# TokTok_WiFi.net
KiCad netlist of a schematic drawn in EAGLE
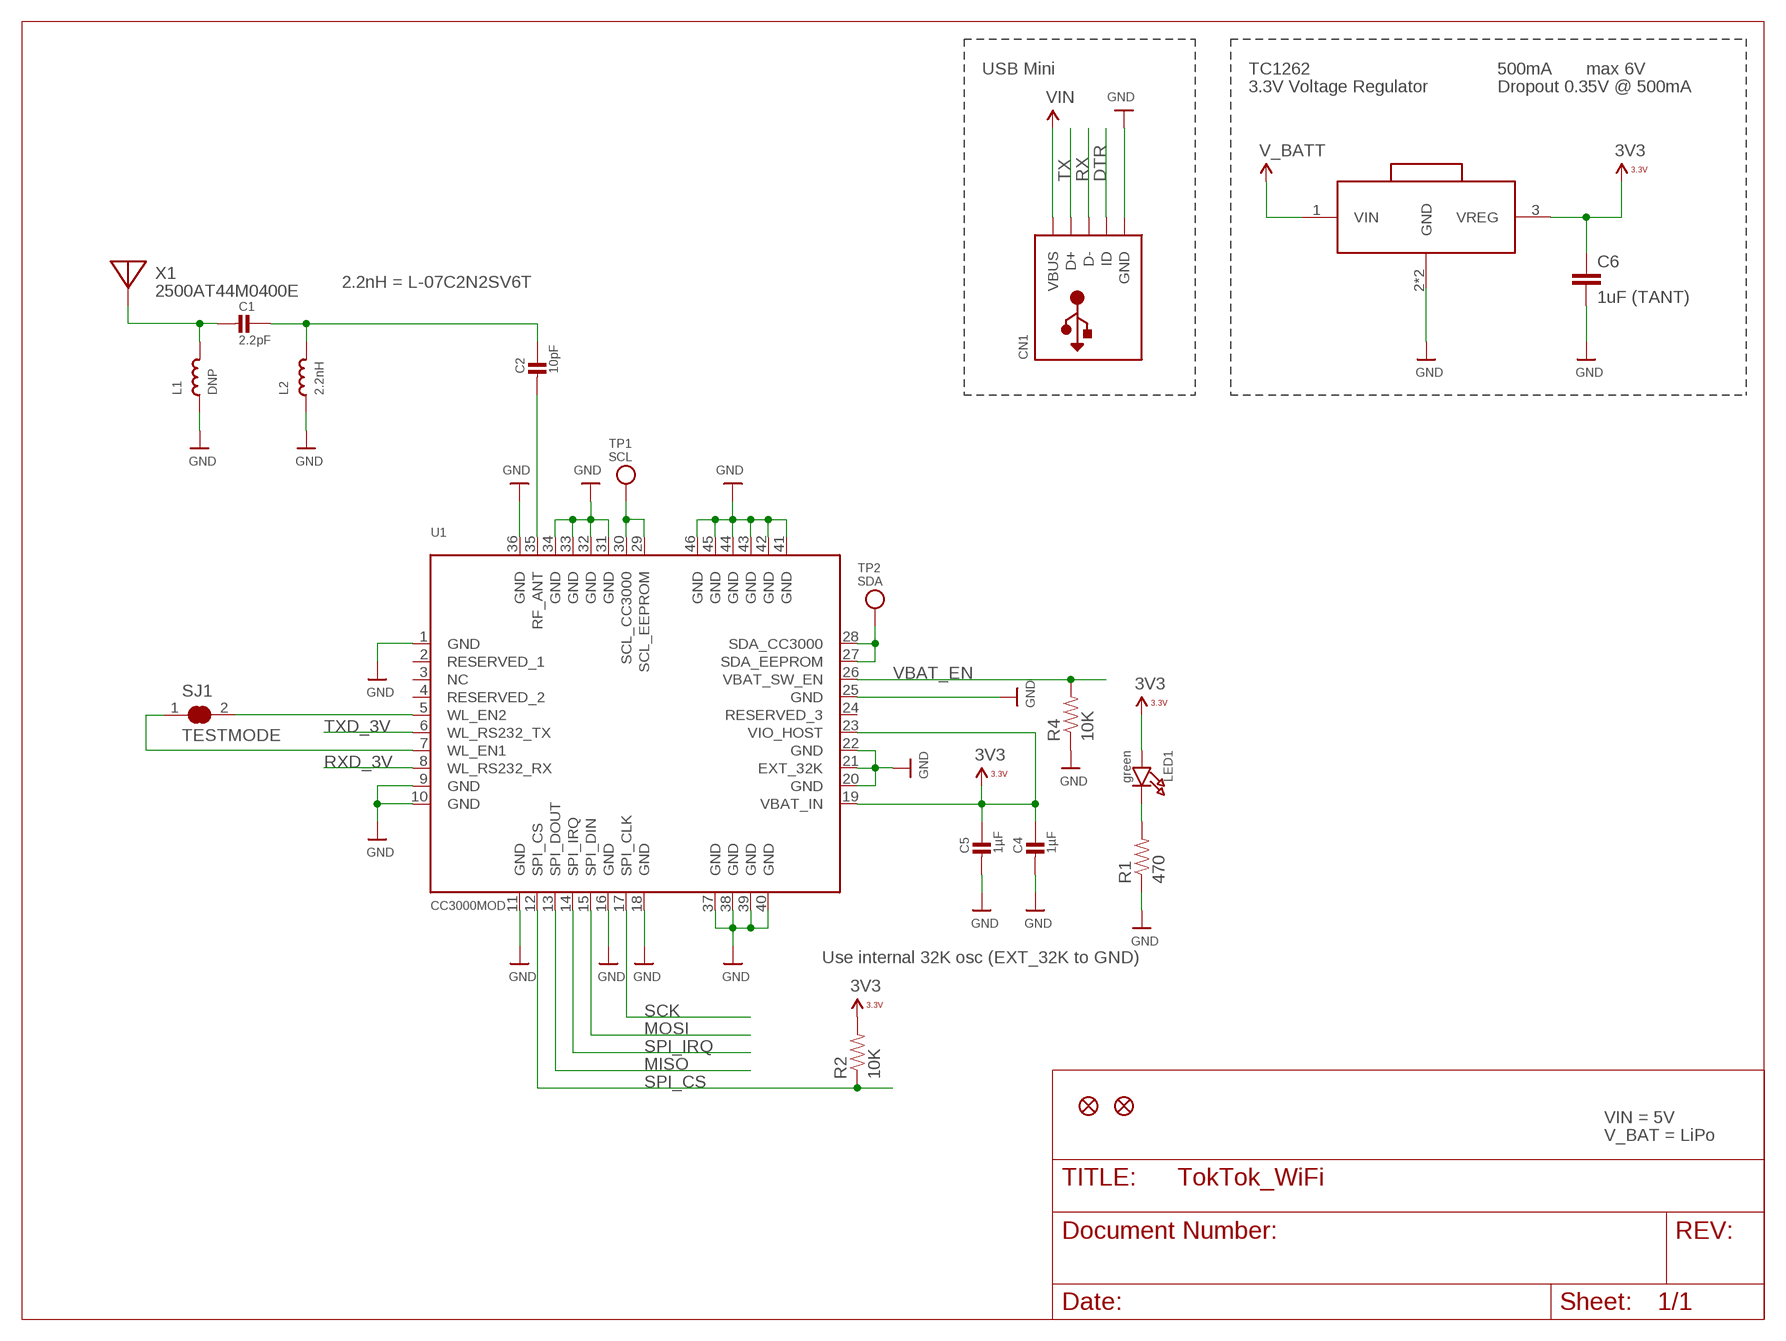
[diagram p0: schematic, sheet 1, part 1 of 2]
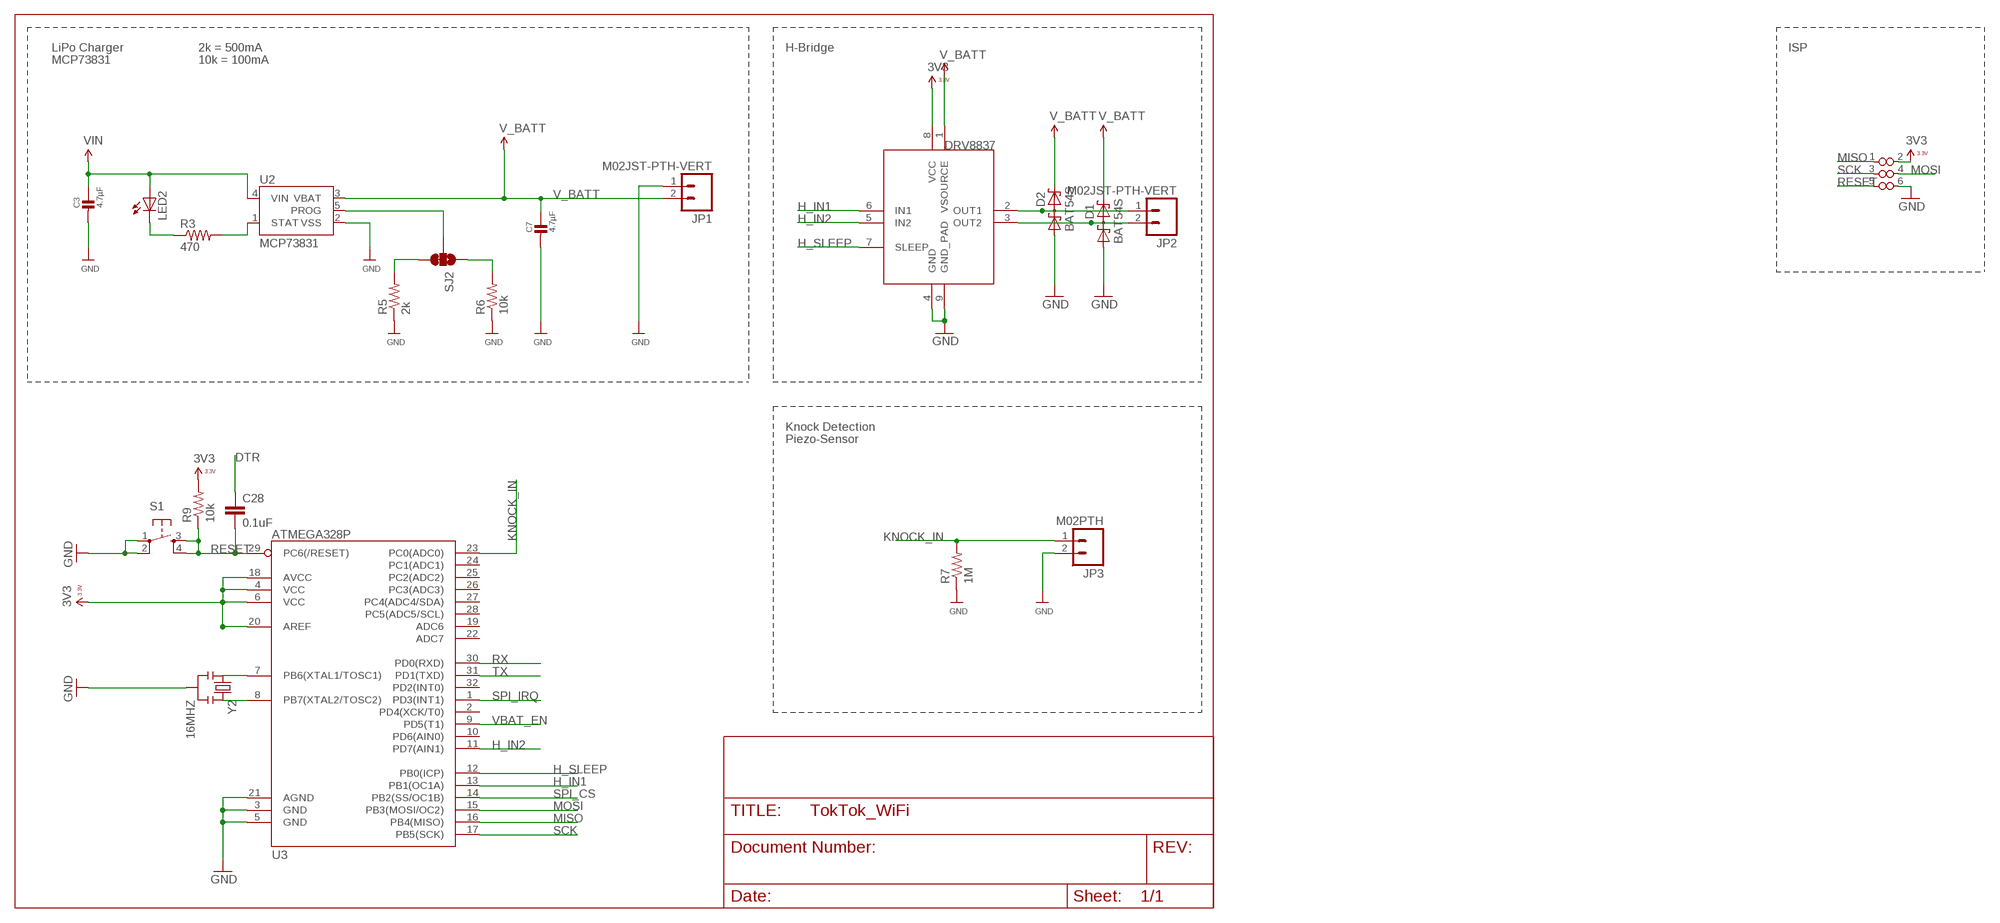
[diagram p1: schematic, sheet 1, part 2 of 2]

(export (version "E")
  (design (tool "Eeschema 10.0.6"))
  (components
    (comp (ref "C1")
      (value "2.2pF")
      (footprint "eagle-import:_0402")
      (libsource (lib "eagle-import") (part "CAP_CERAMIC_0402"))
    )
    (comp (ref "C2")
      (value "10pF")
      (footprint "eagle-import:_0402")
      (libsource (lib "eagle-import") (part "CAP_CERAMIC_0402"))
    )
    (comp (ref "C3")
      (value "4.7µF")
      (footprint "eagle-import:_0805MP")
      (libsource (lib "eagle-import") (part "CAP_CERAMIC_0805MP"))
    )
    (comp (ref "C4")
      (value "1µF")
      (footprint "eagle-import:_0805MP")
      (libsource (lib "eagle-import") (part "CAP_CERAMIC_0805MP"))
    )
    (comp (ref "C5")
      (value "1µF")
      (footprint "eagle-import:_0805MP")
      (libsource (lib "eagle-import") (part "CAP_CERAMIC_0805MP"))
    )
    (comp (ref "C6")
      (value "1uF (TANT)")
      (footprint "eagle-import:1206")
      (libsource (lib "eagle-import") (part "CAP1206"))
    )
    (comp (ref "C7")
      (value "4.7µF")
      (footprint "eagle-import:_0805MP")
      (libsource (lib "eagle-import") (part "CAP_CERAMIC_0805MP"))
    )
    (comp (ref "C28")
      (value "0.1uF")
      (footprint "eagle-import:0805")
      (libsource (lib "eagle-import") (part "CAP0805"))
    )
    (comp (ref "CN1")
      (value "USBMINIB")
      (footprint "eagle-import:USB-MINIB")
      (libsource (lib "eagle-import") (part "USBMINIB"))
    )
    (comp (ref "D1")
      (value "BAT54S")
      (footprint "eagle-import:SOT23")
      (libsource (lib "eagle-import") (part "BAT54S"))
    )
    (comp (ref "D2")
      (value "BAT54S")
      (footprint "eagle-import:SOT23")
      (libsource (lib "eagle-import") (part "BAT54S"))
    )
    (comp (ref "FID1")
      (value "FIDUCIAL\"\"")
      (footprint "eagle-import:FIDUCIAL_1MM")
      (libsource (lib "eagle-import") (part "FIDUCIAL{dblquote}{dblquote}"))
    )
    (comp (ref "FID3")
      (value "FIDUCIAL\"\"")
      (footprint "eagle-import:FIDUCIAL_1MM")
      (fields (field (name "BOM") "EXCLUDE"))
      (libsource (lib "eagle-import") (part "FIDUCIAL{dblquote}{dblquote}"))
    )
    (comp (ref "IC2")
      (value "DRV8837")
      (footprint "eagle-import:WSON-8")
      (libsource (lib "eagle-import") (part "DRV8837"))
    )
    (comp (ref "JP1")
      (value "M02JST-PTH-VERT")
      (footprint "eagle-import:JST-2-PTH-VERT")
      (libsource (lib "eagle-import") (part "M02JST-PTH-VERT"))
    )
    (comp (ref "JP2")
      (value "M02JST-PTH-VERT")
      (footprint "eagle-import:JST-2-PTH-VERT")
      (libsource (lib "eagle-import") (part "M02JST-PTH-VERT"))
    )
    (comp (ref "JP3")
      (value "M02PTH")
      (footprint "eagle-import:1X02")
      (libsource (lib "eagle-import") (part "M02PTH"))
    )
    (comp (ref "L1")
      (value "DNP")
      (footprint "eagle-import:_0402")
      (libsource (lib "eagle-import") (part "INDUCTOR_0402"))
    )
    (comp (ref "L2")
      (value "2.2nH")
      (footprint "eagle-import:_0402")
      (libsource (lib "eagle-import") (part "INDUCTOR_0402"))
    )
    (comp (ref "LED1")
      (value "green")
      (footprint "eagle-import:CHIPLED_0805_NOOUTLINE")
      (libsource (lib "eagle-import") (part "LED0805_NOOUTLINE"))
    )
    (comp (ref "LED2")
      (value "LEDCHIP-LED0805")
      (footprint "eagle-import:CHIP-LED0805")
      (libsource (lib "eagle-import") (part "LEDCHIP-LED0805"))
    )
    (comp (ref "R1")
      (value "470")
      (footprint "eagle-import:0805")
      (libsource (lib "eagle-import") (part "RESISTOR0805-RES"))
    )
    (comp (ref "R2")
      (value "10K")
      (footprint "eagle-import:0805")
      (libsource (lib "eagle-import") (part "RESISTOR0805-RES"))
    )
    (comp (ref "R3")
      (value "470")
      (footprint "eagle-import:0805")
      (libsource (lib "eagle-import") (part "RESISTOR0805-RES"))
    )
    (comp (ref "R4")
      (value "10K")
      (footprint "eagle-import:0805")
      (libsource (lib "eagle-import") (part "RESISTOR0805-RES"))
    )
    (comp (ref "R5")
      (value "2k")
      (footprint "eagle-import:0805")
      (libsource (lib "eagle-import") (part "RESISTOR0805-RES"))
    )
    (comp (ref "R6")
      (value "10k")
      (footprint "eagle-import:0805")
      (libsource (lib "eagle-import") (part "RESISTOR0805-RES"))
    )
    (comp (ref "R7")
      (value "1M")
      (footprint "eagle-import:0805")
      (libsource (lib "eagle-import") (part "RESISTOR0805-RES"))
    )
    (comp (ref "R9")
      (value "10k")
      (footprint "eagle-import:M0805")
      (libsource (lib "eagle-import") (part "R-US_M0805"))
    )
    (comp (ref "S1")
      (value "TAC_SWITCHSMD")
      (footprint "eagle-import:TACTILE-SWITCH-SMD")
      (libsource (lib "eagle-import") (part "TAC_SWITCHSMD"))
    )
    (comp (ref "SJ1")
      (value "TESTMODE")
      (footprint "eagle-import:SOLDERJUMPER_CLOSEDWIRE")
      (libsource (lib "eagle-import") (part "SOLDERJUMPER_CLOSED"))
    )
    (comp (ref "SJ2")
      (value "JUMPER-PAD-3-2OF3_NC_BY_TRACE_SMALL")
      (footprint "eagle-import:PAD-JUMPER-3-2OF3_NC_BY_TRACE_YES_SILK_FULL_BOX")
      (libsource (lib "eagle-import") (part "JUMPER-PAD-3-2OF3_NC_BY_TRACE_SMALL"))
    )
    (comp (ref "TP1")
      (value "SCL")
      (footprint "eagle-import:TESTPOINT_PAD_1MM")
      (libsource (lib "eagle-import") (part "TESTPOINTPAD1MM"))
    )
    (comp (ref "TP2")
      (value "SDA")
      (footprint "eagle-import:TESTPOINT_PAD_1MM")
      (libsource (lib "eagle-import") (part "TESTPOINTPAD1MM"))
    )
    (comp (ref "U$3")
      (value "TC1262")
      (footprint "eagle-import:SOT223")
      (libsource (lib "eagle-import") (part "TC1262"))
    )
    (comp (ref "U$36")
      (value "ISP_POGO")
      (footprint "eagle-import:POGO_ISP")
      (libsource (lib "eagle-import") (part "ISP_POGO"))
    )
    (comp (ref "U1")
      (value "CC3000MOD")
      (footprint "eagle-import:CC3000MOD")
      (libsource (lib "eagle-import") (part "CC3000MOD"))
    )
    (comp (ref "U2")
      (value "MCP73831")
      (footprint "eagle-import:SOT23-5")
      (libsource (lib "eagle-import") (part "MCP73831"))
    )
    (comp (ref "U3")
      (value "ATMEGA328P")
      (footprint "eagle-import:TQFP32-08")
      (libsource (lib "eagle-import") (part "ATMEGA328_SMT"))
    )
    (comp (ref "X1")
      (value "2500AT44M0400E")
      (footprint "eagle-import:ANT_2500AT44M0400")
      (libsource (lib "eagle-import") (part "ANTENNA_JOHANSON_2500AT44M0400"))
    )
    (comp (ref "Y2")
      (value "16MHZ")
      (footprint "eagle-import:RESONATOR-SMD")
      (libsource (lib "eagle-import") (part "RESONATOR8MHZ"))
    )
  )
  (nets
    (net (code "1") (name "/DTR") (class "Default")
      (node (ref "C28") (pin "1") (pinfunction "1_1") (pintype "passive"))
      (node (ref "CN1") (pin "ID") (pinfunction "ID_ID") (pintype "bidirectional"))
    )
    (net (code "2") (name "/H_IN1") (class "Default")
      (node (ref "IC2") (pin "6") (pinfunction "IN1_6") (pintype "bidirectional"))
      (node (ref "U3") (pin "13") (pinfunction "PB1(OC1A)_13") (pintype "bidirectional"))
    )
    (net (code "3") (name "/H_IN2") (class "Default")
      (node (ref "IC2") (pin "5") (pinfunction "IN2_5") (pintype "bidirectional"))
      (node (ref "U3") (pin "11") (pinfunction "PD7(AIN1)_11") (pintype "bidirectional"))
    )
    (net (code "4") (name "/H_SLEEP") (class "Default")
      (node (ref "IC2") (pin "7") (pinfunction "SLEEP_7") (pintype "bidirectional"))
      (node (ref "U3") (pin "12") (pinfunction "PB0(ICP)_12") (pintype "bidirectional"))
    )
    (net (code "5") (name "/KNOCK_IN") (class "Default")
      (node (ref "JP3") (pin "1") (pinfunction "1_1") (pintype "passive"))
      (node (ref "R7") (pin "2") (pinfunction "2_2") (pintype "passive"))
      (node (ref "U3") (pin "23") (pinfunction "PC0(ADC0)_23") (pintype "bidirectional"))
    )
    (net (code "6") (name "/MISO") (class "Default")
      (node (ref "U$36") (pin "1") (pinfunction "MISO_1") (pintype "bidirectional"))
      (node (ref "U1") (pin "13") (pinfunction "SPI_DOUT_13") (pintype "output"))
      (node (ref "U3") (pin "16") (pinfunction "PB4(MISO)_16") (pintype "bidirectional"))
    )
    (net (code "7") (name "/MOSI") (class "Default")
      (node (ref "U$36") (pin "4") (pinfunction "MOSI_4") (pintype "bidirectional"))
      (node (ref "U1") (pin "15") (pinfunction "SPI_DIN_15") (pintype "input"))
      (node (ref "U3") (pin "15") (pinfunction "PB3(MOSI/OC2)_15") (pintype "bidirectional"))
    )
    (net (code "8") (name "/RESET") (class "Default")
      (node (ref "C28") (pin "2") (pinfunction "2_2") (pintype "passive"))
      (node (ref "R9") (pin "1") (pinfunction "1_1") (pintype "passive"))
      (node (ref "S1") (pin "3") (pinfunction "3_3") (pintype "passive"))
      (node (ref "S1") (pin "4") (pinfunction "4_4") (pintype "passive"))
      (node (ref "U$36") (pin "5") (pinfunction "RESET_5") (pintype "bidirectional"))
      (node (ref "U3") (pin "29") (pinfunction "PC6(/RESET)_29") (pintype "bidirectional"))
    )
    (net (code "9") (name "/RX") (class "Default")
      (node (ref "CN1") (pin "D-") (pinfunction "D-_D-") (pintype "bidirectional"))
      (node (ref "U3") (pin "30") (pinfunction "PD0(RXD)_30") (pintype "bidirectional"))
    )
    (net (code "10") (name "/RXD_3V") (class "Default")
      (node (ref "U1") (pin "8") (pinfunction "WL_RS232_RX_8") (pintype "input"))
    )
    (net (code "11") (name "/SCK") (class "Default")
      (node (ref "U$36") (pin "3") (pinfunction "SCK_3") (pintype "bidirectional"))
      (node (ref "U1") (pin "17") (pinfunction "SPI_CLK_17") (pintype "input"))
      (node (ref "U3") (pin "17") (pinfunction "PB5(SCK)_17") (pintype "bidirectional"))
    )
    (net (code "12") (name "/SPI_CS") (class "Default")
      (node (ref "R2") (pin "1") (pinfunction "1_1") (pintype "passive"))
      (node (ref "U1") (pin "12") (pinfunction "SPI_CS_12") (pintype "input"))
      (node (ref "U3") (pin "14") (pinfunction "PB2(SS/OC1B)_14") (pintype "bidirectional"))
    )
    (net (code "13") (name "/SPI_IRQ") (class "Default")
      (node (ref "U1") (pin "14") (pinfunction "SPI_IRQ_14") (pintype "output"))
      (node (ref "U3") (pin "1") (pinfunction "PD3(INT1)_1") (pintype "bidirectional"))
    )
    (net (code "14") (name "/TX") (class "Default")
      (node (ref "CN1") (pin "D+") (pinfunction "D+_D+") (pintype "bidirectional"))
      (node (ref "U3") (pin "31") (pinfunction "PD1(TXD)_31") (pintype "bidirectional"))
    )
    (net (code "15") (name "/TXD_3V") (class "Default")
      (node (ref "U1") (pin "6") (pinfunction "WL_RS232_TX_6") (pintype "output"))
    )
    (net (code "16") (name "/VBAT_EN") (class "Default")
      (node (ref "R4") (pin "2") (pinfunction "2_2") (pintype "passive"))
      (node (ref "U1") (pin "26") (pinfunction "VBAT_SW_EN_26") (pintype "input"))
      (node (ref "U3") (pin "9") (pinfunction "PD5(T1)_9") (pintype "bidirectional"))
    )
    (net (code "17") (name "3V3") (class "Default")
      (node (ref "C4") (pin "1") (pinfunction "1_1") (pintype "passive"))
      (node (ref "C5") (pin "1") (pinfunction "1_1") (pintype "passive"))
      (node (ref "C6") (pin "1") (pinfunction "1_1") (pintype "passive"))
      (node (ref "IC2") (pin "8") (pinfunction "VCC_8") (pintype "bidirectional"))
      (node (ref "LED1") (pin "A") (pinfunction "A_A") (pintype "passive"))
      (node (ref "R2") (pin "2") (pinfunction "2_2") (pintype "passive"))
      (node (ref "R9") (pin "2") (pinfunction "2_2") (pintype "passive"))
      (node (ref "U$3") (pin "3") (pinfunction "VREG_3") (pintype "bidirectional"))
      (node (ref "U$36") (pin "2") (pinfunction "VCC_2") (pintype "bidirectional"))
      (node (ref "U1") (pin "19") (pinfunction "VBAT_IN_19") (pintype "power_in"))
      (node (ref "U1") (pin "23") (pinfunction "VIO_HOST_23") (pintype "power_in"))
      (node (ref "U3") (pin "18") (pinfunction "AVCC_18") (pintype "bidirectional"))
      (node (ref "U3") (pin "20") (pinfunction "AREF_20") (pintype "bidirectional"))
      (node (ref "U3") (pin "4") (pinfunction "VCC_4") (pintype "bidirectional"))
      (node (ref "U3") (pin "6") (pinfunction "VCC_6") (pintype "bidirectional"))
    )
    (net (code "18") (name "GND") (class "Default")
      (node (ref "C3") (pin "2") (pinfunction "2_2") (pintype "passive"))
      (node (ref "C4") (pin "2") (pinfunction "2_2") (pintype "passive"))
      (node (ref "C5") (pin "2") (pinfunction "2_2") (pintype "passive"))
      (node (ref "C6") (pin "2") (pinfunction "2_2") (pintype "passive"))
      (node (ref "C7") (pin "2") (pinfunction "2_2") (pintype "passive"))
      (node (ref "CN1") (pin "GND") (pinfunction "GND_GND") (pintype "power_in"))
      (node (ref "D1") (pin "1") (pinfunction "A1_1") (pintype "passive"))
      (node (ref "D2") (pin "1") (pinfunction "A1_1") (pintype "passive"))
      (node (ref "IC2") (pin "4") (pinfunction "GND_4") (pintype "bidirectional"))
      (node (ref "IC2") (pin "9") (pinfunction "GND_PAD_9") (pintype "bidirectional"))
      (node (ref "JP1") (pin "1") (pinfunction "1_1") (pintype "passive"))
      (node (ref "JP3") (pin "2") (pinfunction "2_2") (pintype "passive"))
      (node (ref "L1") (pin "1") (pinfunction "1_1") (pintype "passive"))
      (node (ref "L2") (pin "1") (pinfunction "1_1") (pintype "passive"))
      (node (ref "R1") (pin "1") (pinfunction "1_1") (pintype "passive"))
      (node (ref "R4") (pin "1") (pinfunction "1_1") (pintype "passive"))
      (node (ref "R5") (pin "1") (pinfunction "1_1") (pintype "passive"))
      (node (ref "R6") (pin "1") (pinfunction "1_1") (pintype "passive"))
      (node (ref "R7") (pin "1") (pinfunction "1_1") (pintype "passive"))
      (node (ref "S1") (pin "1") (pinfunction "1_1") (pintype "passive"))
      (node (ref "S1") (pin "2") (pinfunction "2_2") (pintype "passive"))
      (node (ref "U$3") (pin "2") (pinfunction "GND_2") (pintype "bidirectional"))
      (node (ref "U$3") (pin "4") (pinfunction "GND_4") (pintype "bidirectional"))
      (node (ref "U$36") (pin "6") (pinfunction "GND_6") (pintype "bidirectional"))
      (node (ref "U1") (pin "1") (pinfunction "GND_1") (pintype "power_in"))
      (node (ref "U1") (pin "10") (pinfunction "GND_10") (pintype "power_in"))
      (node (ref "U1") (pin "11") (pinfunction "GND_11") (pintype "power_in"))
      (node (ref "U1") (pin "16") (pinfunction "GND_16") (pintype "power_in"))
      (node (ref "U1") (pin "18") (pinfunction "GND_18") (pintype "power_in"))
      (node (ref "U1") (pin "20") (pinfunction "GND_20") (pintype "power_in"))
      (node (ref "U1") (pin "21") (pinfunction "EXT_32K_21") (pintype "bidirectional"))
      (node (ref "U1") (pin "22") (pinfunction "GND_22") (pintype "power_in"))
      (node (ref "U1") (pin "25") (pinfunction "GND_25") (pintype "power_in"))
      (node (ref "U1") (pin "31") (pinfunction "GND_31") (pintype "power_in"))
      (node (ref "U1") (pin "32") (pinfunction "GND_32") (pintype "power_in"))
      (node (ref "U1") (pin "33") (pinfunction "GND_33") (pintype "power_in"))
      (node (ref "U1") (pin "34") (pinfunction "GND_34") (pintype "power_in"))
      (node (ref "U1") (pin "36") (pinfunction "GND_36") (pintype "power_in"))
      (node (ref "U1") (pin "37") (pinfunction "GND_37") (pintype "power_in"))
      (node (ref "U1") (pin "38") (pinfunction "GND_38") (pintype "power_in"))
      (node (ref "U1") (pin "39") (pinfunction "GND_39") (pintype "power_in"))
      (node (ref "U1") (pin "40") (pinfunction "GND_40") (pintype "power_in"))
      (node (ref "U1") (pin "41") (pinfunction "GND_41") (pintype "power_in"))
      (node (ref "U1") (pin "42") (pinfunction "GND_42") (pintype "power_in"))
      (node (ref "U1") (pin "43") (pinfunction "GND_43") (pintype "power_in"))
      (node (ref "U1") (pin "44") (pinfunction "GND_44") (pintype "power_in"))
      (node (ref "U1") (pin "45") (pinfunction "GND_45") (pintype "power_in"))
      (node (ref "U1") (pin "46") (pinfunction "GND_46") (pintype "power_in"))
      (node (ref "U1") (pin "9") (pinfunction "GND_9") (pintype "power_in"))
      (node (ref "U2") (pin "2") (pinfunction "VSS_2") (pintype "power_in"))
      (node (ref "U3") (pin "21") (pinfunction "AGND_21") (pintype "bidirectional"))
      (node (ref "U3") (pin "3") (pinfunction "GND_3") (pintype "bidirectional"))
      (node (ref "U3") (pin "5") (pinfunction "GND_5") (pintype "bidirectional"))
      (node (ref "Y2") (pin "2") (pinfunction "2_2") (pintype "passive"))
    )
    (net (code "19") (name "Net-(C1-Pad1)") (class "Default")
      (node (ref "C1") (pin "1") (pinfunction "1_1") (pintype "passive"))
      (node (ref "C2") (pin "1") (pinfunction "1_1") (pintype "passive"))
      (node (ref "L2") (pin "2") (pinfunction "2_2") (pintype "passive"))
    )
    (net (code "20") (name "Net-(D1-C1A2)") (class "Default")
      (node (ref "D1") (pin "3") (pinfunction "C1A2_3") (pintype "passive"))
      (node (ref "IC2") (pin "3") (pinfunction "OUT2_3") (pintype "bidirectional"))
      (node (ref "JP2") (pin "2") (pinfunction "2_2") (pintype "passive"))
    )
    (net (code "21") (name "Net-(D2-C1A2)") (class "Default")
      (node (ref "D2") (pin "3") (pinfunction "C1A2_3") (pintype "passive"))
      (node (ref "IC2") (pin "2") (pinfunction "OUT1_2") (pintype "bidirectional"))
      (node (ref "JP2") (pin "1") (pinfunction "1_1") (pintype "passive"))
    )
    (net (code "22") (name "Net-(LED1-PadC)") (class "Default")
      (node (ref "LED1") (pin "C") (pinfunction "C_C") (pintype "passive"))
      (node (ref "R1") (pin "2") (pinfunction "2_2") (pintype "passive"))
    )
    (net (code "23") (name "Net-(LED2-PadC)") (class "Default")
      (node (ref "LED2") (pin "C") (pinfunction "C_C") (pintype "passive"))
      (node (ref "R3") (pin "1") (pinfunction "1_1") (pintype "passive"))
    )
    (net (code "24") (name "Net-(R5-Pad2)") (class "Default")
      (node (ref "R5") (pin "2") (pinfunction "2_2") (pintype "passive"))
      (node (ref "SJ2") (pin "3") (pinfunction "3_3") (pintype "passive"))
    )
    (net (code "25") (name "Net-(R6-Pad2)") (class "Default")
      (node (ref "R6") (pin "2") (pinfunction "2_2") (pintype "passive"))
      (node (ref "SJ2") (pin "1") (pinfunction "1_1") (pintype "passive"))
    )
    (net (code "26") (name "Net-(U1-RF_ANT)") (class "Default")
      (node (ref "C2") (pin "2") (pinfunction "2_2") (pintype "passive"))
      (node (ref "U1") (pin "35") (pinfunction "RF_ANT_35") (pintype "bidirectional"))
    )
    (net (code "27") (name "Net-(U1-SCL_CC3000)") (class "Default")
      (node (ref "TP1") (pin "P$1") (pinfunction "P$1_P$1") (pintype "bidirectional"))
      (node (ref "U1") (pin "29") (pinfunction "SCL_EEPROM_29") (pintype "bidirectional"))
      (node (ref "U1") (pin "30") (pinfunction "SCL_CC3000_30") (pintype "bidirectional"))
    )
    (net (code "28") (name "Net-(U1-SDA_CC3000)") (class "Default")
      (node (ref "TP2") (pin "P$1") (pinfunction "P$1_P$1") (pintype "bidirectional"))
      (node (ref "U1") (pin "27") (pinfunction "SDA_EEPROM_27") (pintype "bidirectional"))
      (node (ref "U1") (pin "28") (pinfunction "SDA_CC3000_28") (pintype "bidirectional"))
    )
    (net (code "29") (name "Net-(U1-WL_EN1)") (class "Default")
      (node (ref "SJ1") (pin "1") (pinfunction "1_1") (pintype "passive"))
      (node (ref "U1") (pin "7") (pinfunction "WL_EN1_7") (pintype "input"))
    )
    (net (code "30") (name "Net-(U1-WL_EN2)") (class "Default")
      (node (ref "SJ1") (pin "2") (pinfunction "2_2") (pintype "passive"))
      (node (ref "U1") (pin "5") (pinfunction "WL_EN2_5") (pintype "input"))
    )
    (net (code "31") (name "Net-(U2-PROG)") (class "Default")
      (node (ref "SJ2") (pin "2") (pinfunction "2_2") (pintype "passive"))
      (node (ref "U2") (pin "5") (pinfunction "PROG_5") (pintype "input"))
    )
    (net (code "32") (name "Net-(U2-STAT)") (class "Default")
      (node (ref "R3") (pin "2") (pinfunction "2_2") (pintype "passive"))
      (node (ref "U2") (pin "1") (pinfunction "STAT_1") (pintype "output"))
    )
    (net (code "33") (name "Net-(U3-PB6(XTAL1{slash}TOSC1))") (class "Default")
      (node (ref "U3") (pin "7") (pinfunction "PB6(XTAL1/TOSC1)_7") (pintype "bidirectional"))
      (node (ref "Y2") (pin "1") (pinfunction "1_1") (pintype "passive"))
    )
    (net (code "34") (name "Net-(U3-PB7(XTAL2{slash}TOSC2))") (class "Default")
      (node (ref "U3") (pin "8") (pinfunction "PB7(XTAL2/TOSC2)_8") (pintype "bidirectional"))
      (node (ref "Y2") (pin "3") (pinfunction "3_3") (pintype "passive"))
    )
    (net (code "35") (name "Net-(X1-P$1)") (class "Default")
      (node (ref "C1") (pin "2") (pinfunction "2_2") (pintype "passive"))
      (node (ref "L1") (pin "2") (pinfunction "2_2") (pintype "passive"))
      (node (ref "X1") (pin "FEED") (pinfunction "P$1_FEED") (pintype "passive"))
    )
    (net (code "36") (name "VIN") (class "Default")
      (node (ref "C3") (pin "1") (pinfunction "1_1") (pintype "passive"))
      (node (ref "CN1") (pin "VBUS") (pinfunction "VBUS_VBUS") (pintype "power_in"))
      (node (ref "LED2") (pin "A") (pinfunction "A_A") (pintype "passive"))
      (node (ref "U2") (pin "4") (pinfunction "VIN_4") (pintype "power_in"))
    )
    (net (code "37") (name "V_BATT") (class "Default")
      (node (ref "C7") (pin "1") (pinfunction "1_1") (pintype "passive"))
      (node (ref "D1") (pin "2") (pinfunction "C2_2") (pintype "passive"))
      (node (ref "D2") (pin "2") (pinfunction "C2_2") (pintype "passive"))
      (node (ref "IC2") (pin "1") (pinfunction "VSOURCE_1") (pintype "bidirectional"))
      (node (ref "JP1") (pin "2") (pinfunction "2_2") (pintype "passive"))
      (node (ref "U$3") (pin "1") (pinfunction "VIN_1") (pintype "bidirectional"))
      (node (ref "U2") (pin "3") (pinfunction "VBAT_3") (pintype "power_in"))
    )
    (net (code "38") (name "unconnected-(U1-NC-Pad3)") (class "Default")
      (node (ref "U1") (pin "3") (pinfunction "NC_3") (pintype "no_connect"))
    )
    (net (code "39") (name "unconnected-(U1-RESERVED_1-Pad2)") (class "Default")
      (node (ref "U1") (pin "2") (pinfunction "RESERVED_1_2") (pintype "bidirectional"))
    )
    (net (code "40") (name "unconnected-(U1-RESERVED_2-Pad4)") (class "Default")
      (node (ref "U1") (pin "4") (pinfunction "RESERVED_2_4") (pintype "bidirectional"))
    )
    (net (code "41") (name "unconnected-(U1-RESERVED_3-Pad24)") (class "Default")
      (node (ref "U1") (pin "24") (pinfunction "RESERVED_3_24") (pintype "bidirectional"))
    )
    (net (code "42") (name "unconnected-(U3-ADC6-Pad19)") (class "Default")
      (node (ref "U3") (pin "19") (pinfunction "ADC6_19") (pintype "bidirectional"))
    )
    (net (code "43") (name "unconnected-(U3-ADC7-Pad22)") (class "Default")
      (node (ref "U3") (pin "22") (pinfunction "ADC7_22") (pintype "bidirectional"))
    )
    (net (code "44") (name "unconnected-(U3-PC1(ADC1)-Pad24)") (class "Default")
      (node (ref "U3") (pin "24") (pinfunction "PC1(ADC1)_24") (pintype "bidirectional"))
    )
    (net (code "45") (name "unconnected-(U3-PC2(ADC2)-Pad25)") (class "Default")
      (node (ref "U3") (pin "25") (pinfunction "PC2(ADC2)_25") (pintype "bidirectional"))
    )
    (net (code "46") (name "unconnected-(U3-PC3(ADC3)-Pad26)") (class "Default")
      (node (ref "U3") (pin "26") (pinfunction "PC3(ADC3)_26") (pintype "bidirectional"))
    )
    (net (code "47") (name "unconnected-(U3-PC4(ADC4{slash}SDA)-Pad27)") (class "Default")
      (node (ref "U3") (pin "27") (pinfunction "PC4(ADC4/SDA)_27") (pintype "bidirectional"))
    )
    (net (code "48") (name "unconnected-(U3-PC5(ADC5{slash}SCL)-Pad28)") (class "Default")
      (node (ref "U3") (pin "28") (pinfunction "PC5(ADC5/SCL)_28") (pintype "bidirectional"))
    )
    (net (code "49") (name "unconnected-(U3-PD2(INT0)-Pad32)") (class "Default")
      (node (ref "U3") (pin "32") (pinfunction "PD2(INT0)_32") (pintype "bidirectional"))
    )
    (net (code "50") (name "unconnected-(U3-PD4(XCK{slash}T0)-Pad2)") (class "Default")
      (node (ref "U3") (pin "2") (pinfunction "PD4(XCK/T0)_2") (pintype "bidirectional"))
    )
    (net (code "51") (name "unconnected-(U3-PD6(AIN0)-Pad10)") (class "Default")
      (node (ref "U3") (pin "10") (pinfunction "PD6(AIN0)_10") (pintype "bidirectional"))
    )
  )
)
